# Program_Counter.net
KiCad netlist of a schematic drawn in Altium Designer
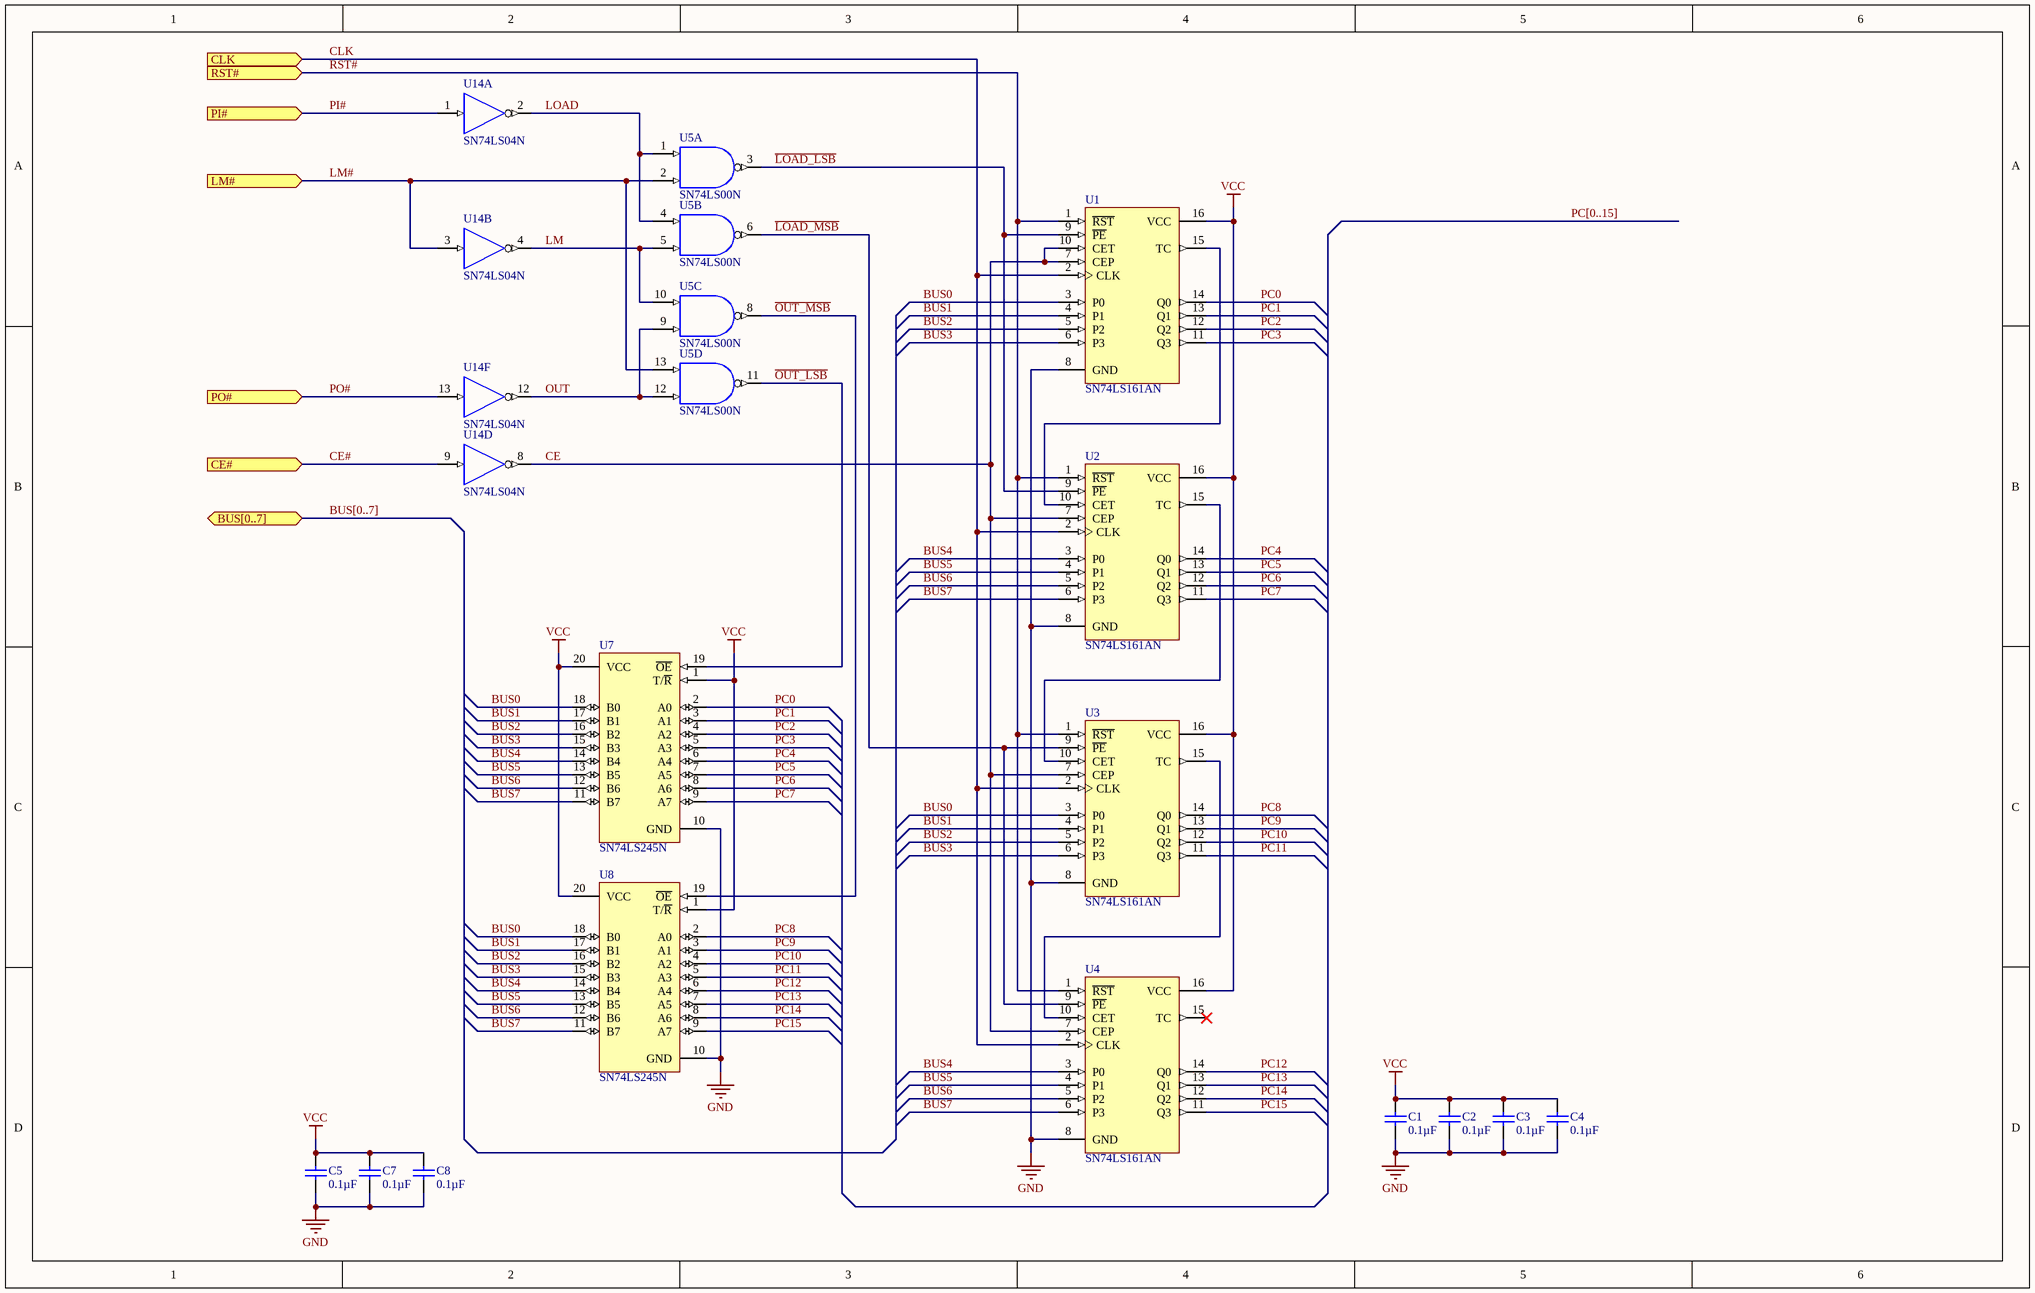
[diagram p0: Program_Counter.SchDoc]

(export (version "E")
  (design (tool "Eeschema 10.0.6"))
  (components
    (comp (ref "C1")
      (value "K104K15X7RF5TL2")
      (footprint "VISH-K104K15X7RF5TL2")
      (description "Ceramic Capacitor, 100 nF, +/- 10%, 50 V, -55 to 125 degC, 2-Pin THD, RoHS, Tape and Reel")
      (fields
        (field (name "MANUFACTURER") "Vishay")
        (field (name "TOLERANCE") "±10%")
        (field (name "CAPACITANCE") "0.1µF")
      )
      (libsource (lib "Altium Content Vault") (part "CAP-NP-2"))
    )
    (comp (ref "C2")
      (value "K104K15X7RF5TL2")
      (footprint "VISH-K104K15X7RF5TL2")
      (description "Ceramic Capacitor, 100 nF, +/- 10%, 50 V, -55 to 125 degC, 2-Pin THD, RoHS, Tape and Reel")
      (fields
        (field (name "MANUFACTURER") "Vishay")
        (field (name "TOLERANCE") "±10%")
        (field (name "CAPACITANCE") "0.1µF")
      )
      (libsource (lib "Altium Content Vault") (part "CAP-NP-2"))
    )
    (comp (ref "C3")
      (value "K104K15X7RF5TL2")
      (footprint "VISH-K104K15X7RF5TL2")
      (description "Ceramic Capacitor, 100 nF, +/- 10%, 50 V, -55 to 125 degC, 2-Pin THD, RoHS, Tape and Reel")
      (fields
        (field (name "MANUFACTURER") "Vishay")
        (field (name "TOLERANCE") "±10%")
        (field (name "CAPACITANCE") "0.1µF")
      )
      (libsource (lib "Altium Content Vault") (part "CAP-NP-2"))
    )
    (comp (ref "C4")
      (value "K104K15X7RF5TL2")
      (footprint "VISH-K104K15X7RF5TL2")
      (description "Ceramic Capacitor, 100 nF, +/- 10%, 50 V, -55 to 125 degC, 2-Pin THD, RoHS, Tape and Reel")
      (fields
        (field (name "MANUFACTURER") "Vishay")
        (field (name "TOLERANCE") "±10%")
        (field (name "CAPACITANCE") "0.1µF")
      )
      (libsource (lib "Altium Content Vault") (part "CAP-NP-2"))
    )
    (comp (ref "C5")
      (value "K104K15X7RF5TL2")
      (footprint "VISH-K104K15X7RF5TL2")
      (description "Ceramic Capacitor, 100 nF, +/- 10%, 50 V, -55 to 125 degC, 2-Pin THD, RoHS, Tape and Reel")
      (fields
        (field (name "MANUFACTURER") "Vishay")
        (field (name "TOLERANCE") "±10%")
        (field (name "CAPACITANCE") "0.1µF")
      )
      (libsource (lib "Altium Content Vault") (part "CAP-NP-2"))
    )
    (comp (ref "C7")
      (value "K104K15X7RF5TL2")
      (footprint "VISH-K104K15X7RF5TL2")
      (description "Ceramic Capacitor, 100 nF, +/- 10%, 50 V, -55 to 125 degC, 2-Pin THD, RoHS, Tape and Reel")
      (fields
        (field (name "MANUFACTURER") "Vishay")
        (field (name "TOLERANCE") "±10%")
        (field (name "CAPACITANCE") "0.1µF")
      )
      (libsource (lib "Altium Content Vault") (part "CAP-NP-2"))
    )
    (comp (ref "C8")
      (value "K104K15X7RF5TL2")
      (footprint "VISH-K104K15X7RF5TL2")
      (description "Ceramic Capacitor, 100 nF, +/- 10%, 50 V, -55 to 125 degC, 2-Pin THD, RoHS, Tape and Reel")
      (fields
        (field (name "MANUFACTURER") "Vishay")
        (field (name "TOLERANCE") "±10%")
        (field (name "CAPACITANCE") "0.1µF")
      )
      (libsource (lib "Altium Content Vault") (part "CAP-NP-2"))
    )
    (comp (ref "U1")
      (value "SN74LS161AN")
      (footprint "N016")
      (description "Synchronous 4-Bit Counter")
      (fields (field (name "PUBLISHER") "Altium Limited"))
      (libsource (lib "TI Logic Counter") (part "SN74LS161AN"))
    )
    (comp (ref "U2")
      (value "SN74LS161AN")
      (footprint "N016")
      (description "Synchronous 4-Bit Counter")
      (fields (field (name "PUBLISHER") "Altium Limited"))
      (libsource (lib "TI Logic Counter") (part "SN74LS161AN"))
    )
    (comp (ref "U3")
      (value "SN74LS161AN")
      (footprint "N016")
      (description "Synchronous 4-Bit Counter")
      (fields (field (name "PUBLISHER") "Altium Limited"))
      (libsource (lib "TI Logic Counter") (part "SN74LS161AN"))
    )
    (comp (ref "U4")
      (value "SN74LS161AN")
      (footprint "N016")
      (description "Synchronous 4-Bit Counter")
      (fields (field (name "PUBLISHER") "Altium Limited"))
      (libsource (lib "TI Logic Counter") (part "SN74LS161AN"))
    )
    (comp (ref "U5")
      (value "SN74LS00N")
      (footprint "N014")
      (description "Quadruple 2-Input Positive-NAND Gate")
      (fields (field (name "PUBLISHER") "Altium Limited"))
      (libsource (lib "") (part "SN74LS00N_1"))
    )
    (comp (ref "U7")
      (value "SN74LS245N")
      (footprint "N020")
      (description "Octal Bus Transceiver with 3-State Outputs")
      (fields (field (name "PUBLISHER") "Altium Limited"))
      (libsource (lib "TI Interface 8-Bit Line Transceiver") (part "SN74LS245N"))
    )
    (comp (ref "U8")
      (value "SN74LS245N")
      (footprint "N020")
      (description "Octal Bus Transceiver with 3-State Outputs")
      (fields (field (name "PUBLISHER") "Altium Limited"))
      (libsource (lib "TI Interface 8-Bit Line Transceiver") (part "SN74LS245N"))
    )
    (comp (ref "U14")
      (value "SN74LS04N")
      (footprint "N014")
      (description "Hex Inverter")
      (fields (field (name "PUBLISHER") "Altium Limited"))
      (libsource (lib "TI Logic Gate 2") (part "SN74LS04N"))
    )
  )
  (nets
    (net (code "1") (name "/BUS0") (class "Default")
      (node (ref "U1") (pin "3") (pinfunction "P0_3") (pintype "input"))
      (node (ref "U3") (pin "3") (pinfunction "P0_3") (pintype "input"))
      (node (ref "U7") (pin "18") (pinfunction "B0_18") (pintype "bidirectional"))
      (node (ref "U8") (pin "18") (pinfunction "B0_18") (pintype "bidirectional"))
    )
    (net (code "2") (name "/BUS1") (class "Default")
      (node (ref "U1") (pin "4") (pinfunction "P1_4") (pintype "input"))
      (node (ref "U3") (pin "4") (pinfunction "P1_4") (pintype "input"))
      (node (ref "U7") (pin "17") (pinfunction "B1_17") (pintype "bidirectional"))
      (node (ref "U8") (pin "17") (pinfunction "B1_17") (pintype "bidirectional"))
    )
    (net (code "3") (name "/BUS2") (class "Default")
      (node (ref "U1") (pin "5") (pinfunction "P2_5") (pintype "input"))
      (node (ref "U3") (pin "5") (pinfunction "P2_5") (pintype "input"))
      (node (ref "U7") (pin "16") (pinfunction "B2_16") (pintype "bidirectional"))
      (node (ref "U8") (pin "16") (pinfunction "B2_16") (pintype "bidirectional"))
    )
    (net (code "4") (name "/BUS3") (class "Default")
      (node (ref "U1") (pin "6") (pinfunction "P3_6") (pintype "input"))
      (node (ref "U3") (pin "6") (pinfunction "P3_6") (pintype "input"))
      (node (ref "U7") (pin "15") (pinfunction "B3_15") (pintype "bidirectional"))
      (node (ref "U8") (pin "15") (pinfunction "B3_15") (pintype "bidirectional"))
    )
    (net (code "5") (name "/BUS4") (class "Default")
      (node (ref "U2") (pin "3") (pinfunction "P0_3") (pintype "input"))
      (node (ref "U4") (pin "3") (pinfunction "P0_3") (pintype "input"))
      (node (ref "U7") (pin "14") (pinfunction "B4_14") (pintype "bidirectional"))
      (node (ref "U8") (pin "14") (pinfunction "B4_14") (pintype "bidirectional"))
    )
    (net (code "6") (name "/BUS5") (class "Default")
      (node (ref "U2") (pin "4") (pinfunction "P1_4") (pintype "input"))
      (node (ref "U4") (pin "4") (pinfunction "P1_4") (pintype "input"))
      (node (ref "U7") (pin "13") (pinfunction "B5_13") (pintype "bidirectional"))
      (node (ref "U8") (pin "13") (pinfunction "B5_13") (pintype "bidirectional"))
    )
    (net (code "7") (name "/BUS6") (class "Default")
      (node (ref "U2") (pin "5") (pinfunction "P2_5") (pintype "input"))
      (node (ref "U4") (pin "5") (pinfunction "P2_5") (pintype "input"))
      (node (ref "U7") (pin "12") (pinfunction "B6_12") (pintype "bidirectional"))
      (node (ref "U8") (pin "12") (pinfunction "B6_12") (pintype "bidirectional"))
    )
    (net (code "8") (name "/BUS7") (class "Default")
      (node (ref "U2") (pin "6") (pinfunction "P3_6") (pintype "input"))
      (node (ref "U4") (pin "6") (pinfunction "P3_6") (pintype "input"))
      (node (ref "U7") (pin "11") (pinfunction "B7_11") (pintype "bidirectional"))
      (node (ref "U8") (pin "11") (pinfunction "B7_11") (pintype "bidirectional"))
    )
    (net (code "10") (name "/CE") (class "Default")
      (node (ref "U1") (pin "10") (pinfunction "CET_10") (pintype "input"))
      (node (ref "U1") (pin "7") (pinfunction "CEP_7") (pintype "input"))
      (node (ref "U14") (pin "8") (pinfunction "Y_8") (pintype "output"))
      (node (ref "U2") (pin "7") (pinfunction "CEP_7") (pintype "input"))
      (node (ref "U3") (pin "7") (pinfunction "CEP_7") (pintype "input"))
      (node (ref "U4") (pin "7") (pinfunction "CEP_7") (pintype "input"))
    )
    (net (code "11") (name "/CE#") (class "Default")
      (node (ref "U14") (pin "9") (pinfunction "A_9") (pintype "input"))
    )
    (net (code "12") (name "/CLK") (class "Default")
      (node (ref "U1") (pin "2") (pinfunction "CLK_2") (pintype "input"))
      (node (ref "U2") (pin "2") (pinfunction "CLK_2") (pintype "input"))
      (node (ref "U3") (pin "2") (pinfunction "CLK_2") (pintype "input"))
      (node (ref "U4") (pin "2") (pinfunction "CLK_2") (pintype "input"))
    )
    (net (code "13") (name "/LM") (class "Default")
      (node (ref "U14") (pin "4") (pinfunction "Y_4") (pintype "output"))
      (node (ref "U5") (pin "10") (pinfunction "B_10") (pintype "input"))
      (node (ref "U5") (pin "5") (pinfunction "B_5") (pintype "input"))
    )
    (net (code "14") (name "/LM#") (class "Default")
      (node (ref "U14") (pin "3") (pinfunction "A_3") (pintype "input"))
      (node (ref "U5") (pin "13") (pinfunction "B_13") (pintype "input"))
      (node (ref "U5") (pin "2") (pinfunction "B_2") (pintype "input"))
    )
    (net (code "15") (name "/LOAD") (class "Default")
      (node (ref "U14") (pin "2") (pinfunction "Y_2") (pintype "output"))
      (node (ref "U5") (pin "1") (pinfunction "A_1") (pintype "input"))
      (node (ref "U5") (pin "4") (pinfunction "A_4") (pintype "input"))
    )
    (net (code "16") (name "/OUT") (class "Default")
      (node (ref "U14") (pin "12") (pinfunction "Y_12") (pintype "output"))
      (node (ref "U5") (pin "12") (pinfunction "A_12") (pintype "input"))
      (node (ref "U5") (pin "9") (pinfunction "A_9") (pintype "input"))
    )
    (net (code "17") (name "/PC0") (class "Default")
      (node (ref "U1") (pin "14") (pinfunction "Q0_14") (pintype "output"))
      (node (ref "U7") (pin "2") (pinfunction "A0_2") (pintype "bidirectional"))
    )
    (net (code "18") (name "/PC1") (class "Default")
      (node (ref "U1") (pin "13") (pinfunction "Q1_13") (pintype "output"))
      (node (ref "U7") (pin "3") (pinfunction "A1_3") (pintype "bidirectional"))
    )
    (net (code "19") (name "/PC2") (class "Default")
      (node (ref "U1") (pin "12") (pinfunction "Q2_12") (pintype "output"))
      (node (ref "U7") (pin "4") (pinfunction "A2_4") (pintype "bidirectional"))
    )
    (net (code "20") (name "/PC3") (class "Default")
      (node (ref "U1") (pin "11") (pinfunction "Q3_11") (pintype "output"))
      (node (ref "U7") (pin "5") (pinfunction "A3_5") (pintype "bidirectional"))
    )
    (net (code "21") (name "/PC4") (class "Default")
      (node (ref "U2") (pin "14") (pinfunction "Q0_14") (pintype "output"))
      (node (ref "U7") (pin "6") (pinfunction "A4_6") (pintype "bidirectional"))
    )
    (net (code "22") (name "/PC5") (class "Default")
      (node (ref "U2") (pin "13") (pinfunction "Q1_13") (pintype "output"))
      (node (ref "U7") (pin "7") (pinfunction "A5_7") (pintype "bidirectional"))
    )
    (net (code "23") (name "/PC6") (class "Default")
      (node (ref "U2") (pin "12") (pinfunction "Q2_12") (pintype "output"))
      (node (ref "U7") (pin "8") (pinfunction "A6_8") (pintype "bidirectional"))
    )
    (net (code "24") (name "/PC7") (class "Default")
      (node (ref "U2") (pin "11") (pinfunction "Q3_11") (pintype "output"))
      (node (ref "U7") (pin "9") (pinfunction "A7_9") (pintype "bidirectional"))
    )
    (net (code "25") (name "/PC8") (class "Default")
      (node (ref "U3") (pin "14") (pinfunction "Q0_14") (pintype "output"))
      (node (ref "U8") (pin "2") (pinfunction "A0_2") (pintype "bidirectional"))
    )
    (net (code "26") (name "/PC9") (class "Default")
      (node (ref "U3") (pin "13") (pinfunction "Q1_13") (pintype "output"))
      (node (ref "U8") (pin "3") (pinfunction "A1_3") (pintype "bidirectional"))
    )
    (net (code "27") (name "/PC10") (class "Default")
      (node (ref "U3") (pin "12") (pinfunction "Q2_12") (pintype "output"))
      (node (ref "U8") (pin "4") (pinfunction "A2_4") (pintype "bidirectional"))
    )
    (net (code "28") (name "/PC11") (class "Default")
      (node (ref "U3") (pin "11") (pinfunction "Q3_11") (pintype "output"))
      (node (ref "U8") (pin "5") (pinfunction "A3_5") (pintype "bidirectional"))
    )
    (net (code "29") (name "/PC12") (class "Default")
      (node (ref "U4") (pin "14") (pinfunction "Q0_14") (pintype "output"))
      (node (ref "U8") (pin "6") (pinfunction "A4_6") (pintype "bidirectional"))
    )
    (net (code "30") (name "/PC13") (class "Default")
      (node (ref "U4") (pin "13") (pinfunction "Q1_13") (pintype "output"))
      (node (ref "U8") (pin "7") (pinfunction "A5_7") (pintype "bidirectional"))
    )
    (net (code "31") (name "/PC14") (class "Default")
      (node (ref "U4") (pin "12") (pinfunction "Q2_12") (pintype "output"))
      (node (ref "U8") (pin "8") (pinfunction "A6_8") (pintype "bidirectional"))
    )
    (net (code "32") (name "/PC15") (class "Default")
      (node (ref "U4") (pin "11") (pinfunction "Q3_11") (pintype "output"))
      (node (ref "U8") (pin "9") (pinfunction "A7_9") (pintype "bidirectional"))
    )
    (net (code "34") (name "/PI#") (class "Default")
      (node (ref "U14") (pin "1") (pinfunction "A_1") (pintype "input"))
    )
    (net (code "35") (name "/PO#") (class "Default")
      (node (ref "U14") (pin "13") (pinfunction "A_13") (pintype "input"))
    )
    (net (code "36") (name "/RST#") (class "Default")
      (node (ref "U1") (pin "1") (pinfunction "~{RST}_1") (pintype "input"))
      (node (ref "U2") (pin "1") (pinfunction "~{RST}_1") (pintype "input"))
      (node (ref "U3") (pin "1") (pinfunction "~{RST}_1") (pintype "input"))
      (node (ref "U4") (pin "1") (pinfunction "~{RST}_1") (pintype "input"))
    )
    (net (code "37") (name "/~{LOAD_LSB}") (class "Default")
      (node (ref "U1") (pin "9") (pinfunction "~{PE}_9") (pintype "input"))
      (node (ref "U2") (pin "9") (pinfunction "~{PE}_9") (pintype "input"))
      (node (ref "U5") (pin "3") (pinfunction "Y_3") (pintype "output"))
    )
    (net (code "38") (name "/~{LOAD_MSB}") (class "Default")
      (node (ref "U3") (pin "9") (pinfunction "~{PE}_9") (pintype "input"))
      (node (ref "U4") (pin "9") (pinfunction "~{PE}_9") (pintype "input"))
      (node (ref "U5") (pin "6") (pinfunction "Y_6") (pintype "output"))
    )
    (net (code "39") (name "/~{OUT_LSB}") (class "Default")
      (node (ref "U5") (pin "11") (pinfunction "Y_11") (pintype "output"))
      (node (ref "U7") (pin "19") (pinfunction "~{OE}_19") (pintype "input"))
    )
    (net (code "40") (name "/~{OUT_MSB}") (class "Default")
      (node (ref "U5") (pin "8") (pinfunction "Y_8") (pintype "output"))
      (node (ref "U8") (pin "19") (pinfunction "~{OE}_19") (pintype "input"))
    )
    (net (code "41") (name "GND") (class "Default")
      (node (ref "C1") (pin "2") (pinfunction "2_2") (pintype "passive"))
      (node (ref "C2") (pin "2") (pinfunction "2_2") (pintype "passive"))
      (node (ref "C3") (pin "2") (pinfunction "2_2") (pintype "passive"))
      (node (ref "C4") (pin "2") (pinfunction "2_2") (pintype "passive"))
      (node (ref "C5") (pin "2") (pinfunction "2_2") (pintype "passive"))
      (node (ref "C7") (pin "2") (pinfunction "2_2") (pintype "passive"))
      (node (ref "C8") (pin "2") (pinfunction "2_2") (pintype "passive"))
      (node (ref "U1") (pin "8") (pinfunction "GND_8") (pintype "power_in"))
      (node (ref "U14") (pin "7") (pinfunction "GND_7") (pintype "power_in"))
      (node (ref "U2") (pin "8") (pinfunction "GND_8") (pintype "power_in"))
      (node (ref "U3") (pin "8") (pinfunction "GND_8") (pintype "power_in"))
      (node (ref "U4") (pin "8") (pinfunction "GND_8") (pintype "power_in"))
      (node (ref "U5") (pin "7") (pinfunction "GND_7") (pintype "power_in"))
      (node (ref "U7") (pin "10") (pinfunction "GND_10") (pintype "power_in"))
      (node (ref "U8") (pin "10") (pinfunction "GND_10") (pintype "power_in"))
    )
    (net (code "42") (name "Net-(U1-TC)") (class "Default")
      (node (ref "U1") (pin "15") (pinfunction "TC_15") (pintype "output"))
      (node (ref "U2") (pin "10") (pinfunction "CET_10") (pintype "input"))
    )
    (net (code "43") (name "Net-(U2-TC)") (class "Default")
      (node (ref "U2") (pin "15") (pinfunction "TC_15") (pintype "output"))
      (node (ref "U3") (pin "10") (pinfunction "CET_10") (pintype "input"))
    )
    (net (code "44") (name "Net-(U3-TC)") (class "Default")
      (node (ref "U3") (pin "15") (pinfunction "TC_15") (pintype "output"))
      (node (ref "U4") (pin "10") (pinfunction "CET_10") (pintype "input"))
    )
    (net (code "45") (name "VCC") (class "Default")
      (node (ref "C1") (pin "1") (pinfunction "1_1") (pintype "passive"))
      (node (ref "C2") (pin "1") (pinfunction "1_1") (pintype "passive"))
      (node (ref "C3") (pin "1") (pinfunction "1_1") (pintype "passive"))
      (node (ref "C4") (pin "1") (pinfunction "1_1") (pintype "passive"))
      (node (ref "C5") (pin "1") (pinfunction "1_1") (pintype "passive"))
      (node (ref "C7") (pin "1") (pinfunction "1_1") (pintype "passive"))
      (node (ref "C8") (pin "1") (pinfunction "1_1") (pintype "passive"))
      (node (ref "U1") (pin "16") (pinfunction "VCC_16") (pintype "power_in"))
      (node (ref "U14") (pin "14") (pinfunction "VCC_14") (pintype "power_in"))
      (node (ref "U2") (pin "16") (pinfunction "VCC_16") (pintype "power_in"))
      (node (ref "U3") (pin "16") (pinfunction "VCC_16") (pintype "power_in"))
      (node (ref "U4") (pin "16") (pinfunction "VCC_16") (pintype "power_in"))
      (node (ref "U5") (pin "14") (pinfunction "VCC_14") (pintype "power_in"))
      (node (ref "U7") (pin "1") (pinfunction "T/~{R}_1") (pintype "input"))
      (node (ref "U7") (pin "20") (pinfunction "VCC_20") (pintype "power_in"))
      (node (ref "U8") (pin "1") (pinfunction "T/~{R}_1") (pintype "input"))
      (node (ref "U8") (pin "20") (pinfunction "VCC_20") (pintype "power_in"))
    )
    (net (code "46") (name "unconnected-(U4-TC-Pad15)") (class "Default")
      (node (ref "U4") (pin "15") (pinfunction "TC_15") (pintype "output+no_connect"))
    )
  )
)
